# Sheet1.net
KiCad netlist of a schematic drawn in Altium Designer
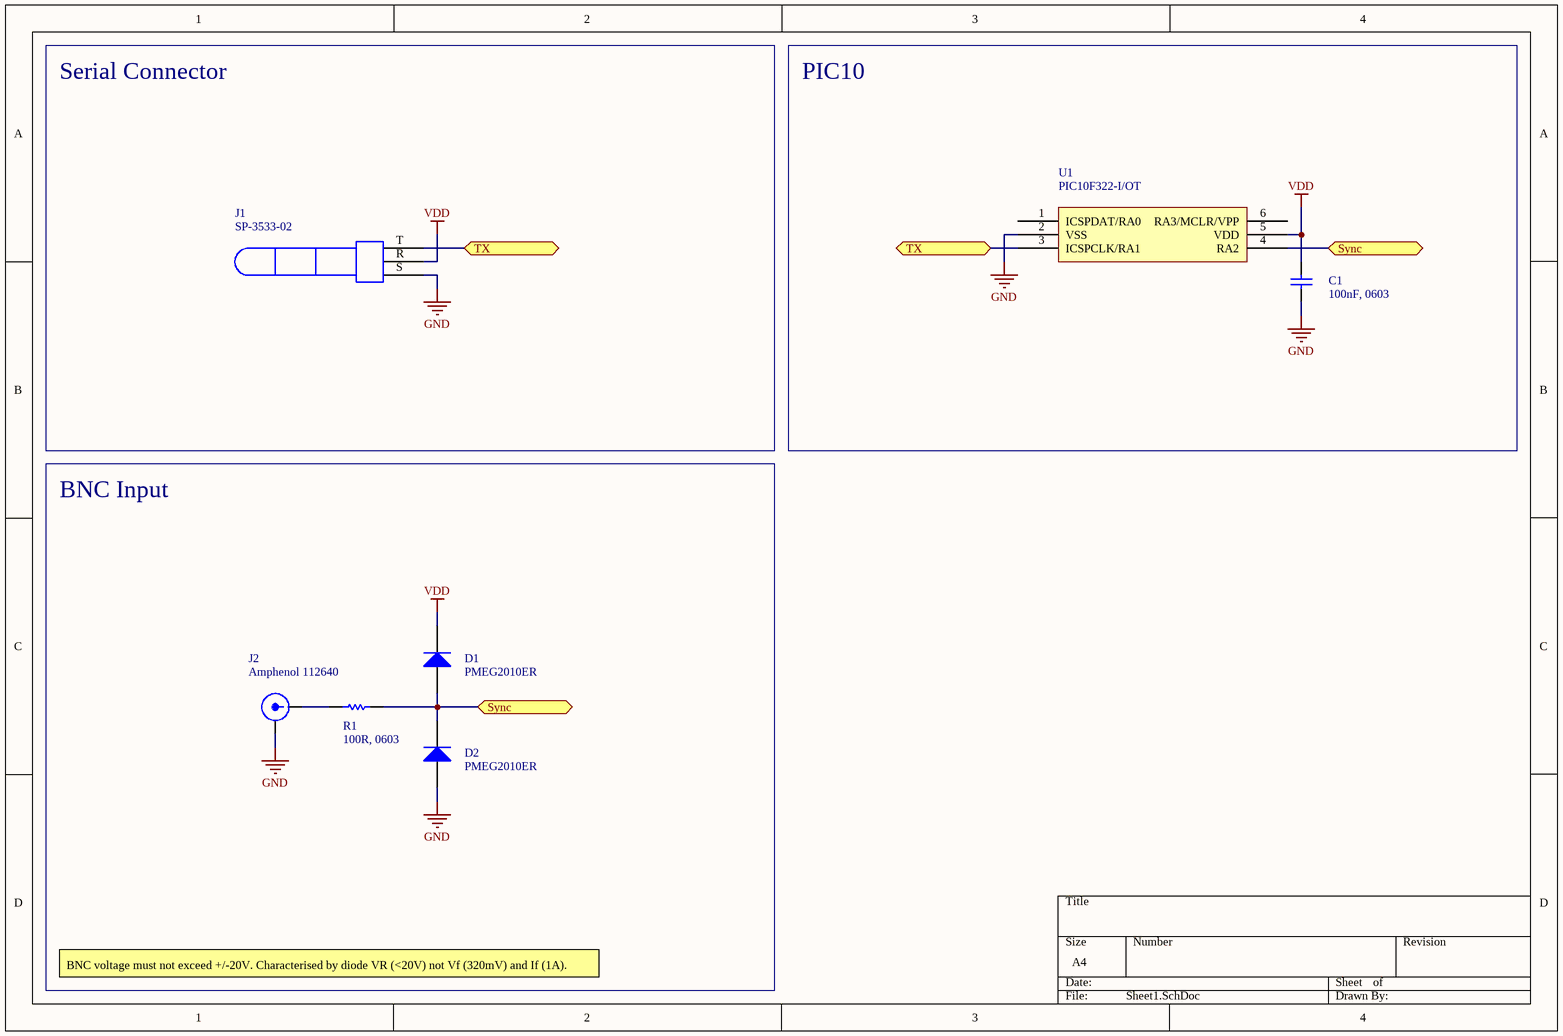
[diagram p0: Sheet1.SchDoc]

(export (version "E")
  (design (tool "Eeschema 10.0.6"))
  (components
    (comp (ref "C1")
      (value "100nF, 0603")
      (footprint "Capacitor 0603")
      (libsource (lib "x-io") (part "Capacitor"))
    )
    (comp (ref "D1") (value "PMEG2010ER") (footprint "SOD-123") (libsource (lib "x-io") (part "Diode")))
    (comp (ref "D2") (value "PMEG2010ER") (footprint "SOD-123") (libsource (lib "x-io") (part "Diode")))
    (comp (ref "J1")
      (value "SP-3533-02")
      (footprint "SP-3533-02")
      (libsource (lib "x-io") (part "SP-3533-02"))
    )
    (comp (ref "J2")
      (value "Amphenol 112640")
      (footprint "Amphenol 112640")
      (libsource (lib "x-io") (part "BNC"))
    )
    (comp (ref "R1")
      (value "100R, 0603")
      (footprint "Resistor 0603")
      (libsource (lib "x-io") (part "Resistor"))
    )
    (comp (ref "U1")
      (value "PIC10F322-I/OT")
      (footprint "SOT-23-6")
      (libsource (lib "x-io") (part "PIC10F322-I/OT"))
    )
  )
  (nets
    (net (code "1") (name "/Sync") (class "Default")
      (node (ref "D1") (pin "A") (pinfunction "A_A") (pintype "passive"))
      (node (ref "D2") (pin "K") (pinfunction "K_K") (pintype "passive"))
      (node (ref "R1") (pin "2") (pinfunction "2_2") (pintype "passive"))
      (node (ref "U1") (pin "4") (pinfunction "RA2_4") (pintype "passive"))
    )
    (net (code "2") (name "/TX") (class "Default")
      (node (ref "J1") (pin "T") (pinfunction "T_T") (pintype "passive"))
      (node (ref "U1") (pin "3") (pinfunction "ICSPCLK/RA1_3") (pintype "passive"))
    )
    (net (code "3") (name "GND") (class "Default")
      (node (ref "C1") (pin "1") (pinfunction "1_1") (pintype "passive"))
      (node (ref "D2") (pin "A") (pinfunction "A_A") (pintype "passive"))
      (node (ref "J1") (pin "S") (pinfunction "S_S") (pintype "passive"))
      (node (ref "J2") (pin "Shield") (pinfunction "Shield_Shield") (pintype "passive"))
      (node (ref "U1") (pin "2") (pinfunction "VSS_2") (pintype "passive"))
    )
    (net (code "4") (name "Net-(J2-PadSignal)") (class "Default")
      (node (ref "J2") (pin "Signal") (pinfunction "Signal_Signal") (pintype "passive"))
      (node (ref "R1") (pin "1") (pinfunction "1_1") (pintype "passive"))
    )
    (net (code "5") (name "VDD") (class "Default")
      (node (ref "C1") (pin "2") (pinfunction "2_2") (pintype "passive"))
      (node (ref "D1") (pin "K") (pinfunction "K_K") (pintype "passive"))
      (node (ref "J1") (pin "R") (pinfunction "R_R") (pintype "passive"))
      (node (ref "U1") (pin "5") (pinfunction "VDD_5") (pintype "passive"))
    )
    (net (code "6") (name "unconnected-(U1-ICSPDAT{slash}RA0-Pad1)") (class "Default")
      (node (ref "U1") (pin "1") (pinfunction "ICSPDAT/RA0_1") (pintype "passive"))
    )
    (net (code "7") (name "unconnected-(U1-RA3{slash}MCLR{slash}VPP-Pad6)") (class "Default")
      (node (ref "U1") (pin "6") (pinfunction "RA3/MCLR/VPP_6") (pintype "passive"))
    )
  )
)
